# ReuseBlock_opa2450_2024-11-16.net
KiCad netlist of a schematic drawn in EasyEDA Pro
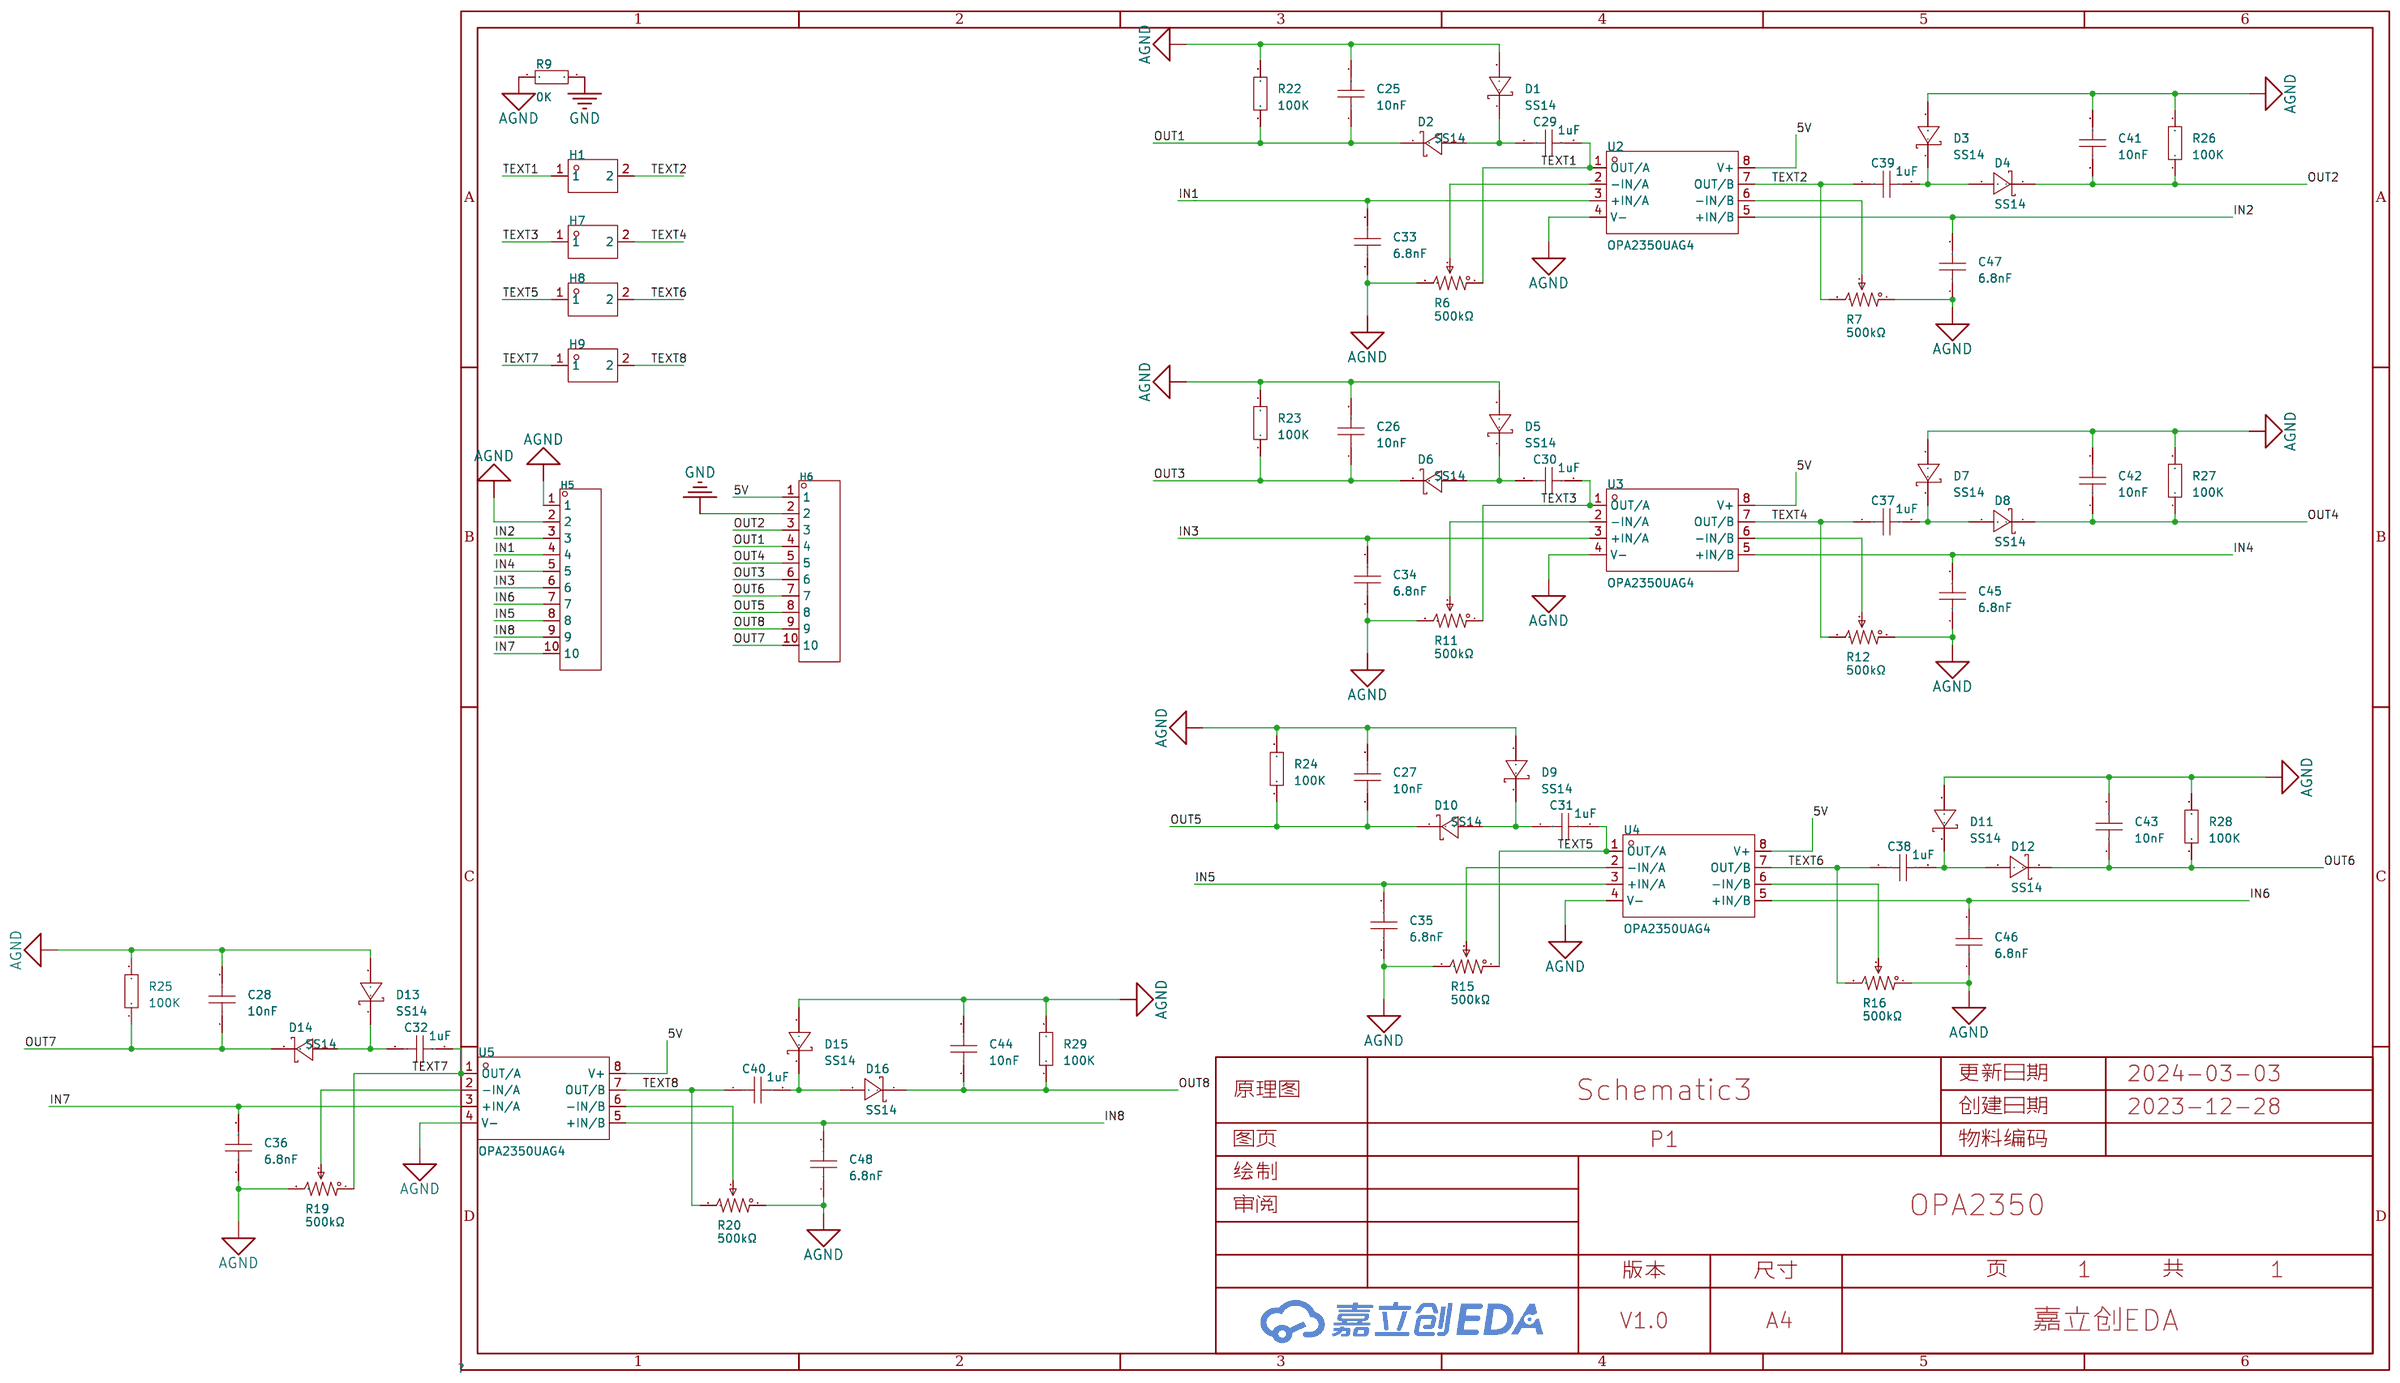
[diagram p0: schematic sheet]

(export (version "E")
  (design (tool "Eeschema 10.0.6"))
  (components
    (comp (ref "C25")
      (value "10nF")
      (footprint "easyedapro:C0603")
      (libsource (lib "easyedapro") (part "CapAcitance"))
    )
    (comp (ref "C26")
      (value "10nF")
      (footprint "easyedapro:C0603")
      (libsource (lib "easyedapro") (part "CapAcitance"))
    )
    (comp (ref "C27")
      (value "10nF")
      (footprint "easyedapro:C0603")
      (libsource (lib "easyedapro") (part "CapAcitance"))
    )
    (comp (ref "C28")
      (value "10nF")
      (footprint "easyedapro:C0603")
      (libsource (lib "easyedapro") (part "CapAcitance"))
    )
    (comp (ref "C29")
      (value "1uF")
      (footprint "easyedapro:C0603")
      (libsource (lib "easyedapro") (part "CapAcitance"))
    )
    (comp (ref "C30")
      (value "1uF")
      (footprint "easyedapro:C0603")
      (libsource (lib "easyedapro") (part "CapAcitance"))
    )
    (comp (ref "C31")
      (value "1uF")
      (footprint "easyedapro:C0603")
      (libsource (lib "easyedapro") (part "CapAcitance"))
    )
    (comp (ref "C32")
      (value "1uF")
      (footprint "easyedapro:C0603")
      (libsource (lib "easyedapro") (part "CapAcitance"))
    )
    (comp (ref "C33")
      (value "6.8nF")
      (footprint "easyedapro:C0603")
      (libsource (lib "easyedapro") (part "CapAcitance"))
    )
    (comp (ref "C34")
      (value "6.8nF")
      (footprint "easyedapro:C0603")
      (libsource (lib "easyedapro") (part "CapAcitance"))
    )
    (comp (ref "C35")
      (value "6.8nF")
      (footprint "easyedapro:C0603")
      (libsource (lib "easyedapro") (part "CapAcitance"))
    )
    (comp (ref "C36")
      (value "6.8nF")
      (footprint "easyedapro:C0603")
      (libsource (lib "easyedapro") (part "CapAcitance"))
    )
    (comp (ref "C37")
      (value "1uF")
      (footprint "easyedapro:C0603")
      (libsource (lib "easyedapro") (part "CapAcitance"))
    )
    (comp (ref "C38")
      (value "1uF")
      (footprint "easyedapro:C0603")
      (libsource (lib "easyedapro") (part "CapAcitance"))
    )
    (comp (ref "C39")
      (value "1uF")
      (footprint "easyedapro:C0603")
      (libsource (lib "easyedapro") (part "CapAcitance"))
    )
    (comp (ref "C40")
      (value "1uF")
      (footprint "easyedapro:C0603")
      (libsource (lib "easyedapro") (part "CapAcitance"))
    )
    (comp (ref "C41")
      (value "10nF")
      (footprint "easyedapro:C0603")
      (libsource (lib "easyedapro") (part "CapAcitance"))
    )
    (comp (ref "C42")
      (value "10nF")
      (footprint "easyedapro:C0603")
      (libsource (lib "easyedapro") (part "CapAcitance"))
    )
    (comp (ref "C43")
      (value "10nF")
      (footprint "easyedapro:C0603")
      (libsource (lib "easyedapro") (part "CapAcitance"))
    )
    (comp (ref "C44")
      (value "10nF")
      (footprint "easyedapro:C0603")
      (libsource (lib "easyedapro") (part "CapAcitance"))
    )
    (comp (ref "C45")
      (value "6.8nF")
      (footprint "easyedapro:C0603")
      (libsource (lib "easyedapro") (part "CapAcitance"))
    )
    (comp (ref "C46")
      (value "6.8nF")
      (footprint "easyedapro:C0603")
      (libsource (lib "easyedapro") (part "CapAcitance"))
    )
    (comp (ref "C47")
      (value "6.8nF")
      (footprint "easyedapro:C0603")
      (libsource (lib "easyedapro") (part "CapAcitance"))
    )
    (comp (ref "C48")
      (value "6.8nF")
      (footprint "easyedapro:C0603")
      (libsource (lib "easyedapro") (part "CapAcitance"))
    )
    (comp (ref "D1")
      (value "SS14")
      (fields (field (name "Manufacturer") "MDD"))
      (libsource (lib "easyedapro") (part "SS14-XZ"))
    )
    (comp (ref "D2")
      (value "SS14")
      (fields (field (name "Manufacturer") "MDD"))
      (libsource (lib "easyedapro") (part "SS14-XZ"))
    )
    (comp (ref "D3")
      (value "SS14")
      (fields (field (name "Manufacturer") "MDD"))
      (libsource (lib "easyedapro") (part "SS14-XZ"))
    )
    (comp (ref "D4")
      (value "SS14")
      (fields (field (name "Manufacturer") "MDD"))
      (libsource (lib "easyedapro") (part "SS14-XZ"))
    )
    (comp (ref "D5")
      (value "SS14")
      (fields (field (name "Manufacturer") "MDD"))
      (libsource (lib "easyedapro") (part "SS14-XZ"))
    )
    (comp (ref "D6")
      (value "SS14")
      (fields (field (name "Manufacturer") "MDD"))
      (libsource (lib "easyedapro") (part "SS14-XZ"))
    )
    (comp (ref "D7")
      (value "SS14")
      (fields (field (name "Manufacturer") "MDD"))
      (libsource (lib "easyedapro") (part "SS14-XZ"))
    )
    (comp (ref "D8")
      (value "SS14")
      (fields (field (name "Manufacturer") "MDD"))
      (libsource (lib "easyedapro") (part "SS14-XZ"))
    )
    (comp (ref "D9")
      (value "SS14")
      (fields (field (name "Manufacturer") "MDD"))
      (libsource (lib "easyedapro") (part "SS14-XZ"))
    )
    (comp (ref "D10")
      (value "SS14")
      (fields (field (name "Manufacturer") "MDD"))
      (libsource (lib "easyedapro") (part "SS14-XZ"))
    )
    (comp (ref "D11")
      (value "SS14")
      (fields (field (name "Manufacturer") "MDD"))
      (libsource (lib "easyedapro") (part "SS14-XZ"))
    )
    (comp (ref "D12")
      (value "SS14")
      (fields (field (name "Manufacturer") "MDD"))
      (libsource (lib "easyedapro") (part "SS14-XZ"))
    )
    (comp (ref "D13")
      (value "SS14")
      (fields (field (name "Manufacturer") "MDD"))
      (libsource (lib "easyedapro") (part "SS14-XZ"))
    )
    (comp (ref "D14")
      (value "SS14")
      (fields (field (name "Manufacturer") "MDD"))
      (libsource (lib "easyedapro") (part "SS14-XZ"))
    )
    (comp (ref "D15")
      (value "SS14")
      (fields (field (name "Manufacturer") "MDD"))
      (libsource (lib "easyedapro") (part "SS14-XZ"))
    )
    (comp (ref "D16")
      (value "SS14")
      (fields (field (name "Manufacturer") "MDD"))
      (libsource (lib "easyedapro") (part "SS14-XZ"))
    )
    (comp (ref "H1")
      (value "~")
      (footprint "easyedapro:HDR-TH_2P-P2.54-V-M-2")
      (libsource (lib "easyedapro") (part "HDR-M-2.54_2x1"))
    )
    (comp (ref "H5")
      (value "~")
      (footprint "easyedapro:HDR-TH_10P-P2.54-V-M-1")
      (libsource (lib "easyedapro") (part "Header-Male-2.54_1x10"))
    )
    (comp (ref "H6")
      (value "~")
      (footprint "easyedapro:HDR-TH_10P-P2.54-V-M-1")
      (libsource (lib "easyedapro") (part "Header-Male-2.54_1x10"))
    )
    (comp (ref "H7")
      (value "~")
      (footprint "easyedapro:HDR-TH_2P-P2.54-V-M-2")
      (libsource (lib "easyedapro") (part "HDR-M-2.54_2x1"))
    )
    (comp (ref "H8")
      (value "~")
      (footprint "easyedapro:HDR-TH_2P-P2.54-V-M-2")
      (libsource (lib "easyedapro") (part "HDR-M-2.54_2x1"))
    )
    (comp (ref "H9")
      (value "~")
      (footprint "easyedapro:HDR-TH_2P-P2.54-V-M-2")
      (libsource (lib "easyedapro") (part "HDR-M-2.54_2x1"))
    )
    (comp (ref "R6")
      (value "500kΩ")
      (footprint "easyedapro:RES-ADJ-TH_3P-L9.5-W4.85-P2.50-BL-BS")
      (description "阻值:500kΩ;精度:±10%;")
      (fields (field (name "Manufacturer Part") "3296W-1-504") (field (name "Manufacturer") "BOCHEN(博晨)"))
      (libsource (lib "easyedapro") (part "3296W-1-504"))
    )
    (comp (ref "R7")
      (value "500kΩ")
      (footprint "easyedapro:RES-ADJ-TH_3P-L9.5-W4.85-P2.50-BL-BS")
      (description "阻值:500kΩ;精度:±10%;")
      (fields (field (name "Manufacturer Part") "3296W-1-504") (field (name "Manufacturer") "BOCHEN(博晨)"))
      (libsource (lib "easyedapro") (part "3296W-1-504"))
    )
    (comp (ref "R9") (value "0K") (footprint "easyedapro:R0603") (libsource (lib "easyedapro") (part "电阻")))
    (comp (ref "R11")
      (value "500kΩ")
      (footprint "easyedapro:RES-ADJ-TH_3P-L9.5-W4.85-P2.50-BL-BS")
      (description "阻值:500kΩ;精度:±10%;")
      (fields (field (name "Manufacturer Part") "3296W-1-504") (field (name "Manufacturer") "BOCHEN(博晨)"))
      (libsource (lib "easyedapro") (part "3296W-1-504"))
    )
    (comp (ref "R12")
      (value "500kΩ")
      (footprint "easyedapro:RES-ADJ-TH_3P-L9.5-W4.85-P2.50-BL-BS")
      (description "阻值:500kΩ;精度:±10%;")
      (fields (field (name "Manufacturer Part") "3296W-1-504") (field (name "Manufacturer") "BOCHEN(博晨)"))
      (libsource (lib "easyedapro") (part "3296W-1-504"))
    )
    (comp (ref "R15")
      (value "500kΩ")
      (footprint "easyedapro:RES-ADJ-TH_3P-L9.5-W4.85-P2.50-BL-BS")
      (description "阻值:500kΩ;精度:±10%;")
      (fields (field (name "Manufacturer Part") "3296W-1-504") (field (name "Manufacturer") "BOCHEN(博晨)"))
      (libsource (lib "easyedapro") (part "3296W-1-504"))
    )
    (comp (ref "R16")
      (value "500kΩ")
      (footprint "easyedapro:RES-ADJ-TH_3P-L9.5-W4.85-P2.50-BL-BS")
      (description "阻值:500kΩ;精度:±10%;")
      (fields (field (name "Manufacturer Part") "3296W-1-504") (field (name "Manufacturer") "BOCHEN(博晨)"))
      (libsource (lib "easyedapro") (part "3296W-1-504"))
    )
    (comp (ref "R19")
      (value "500kΩ")
      (footprint "easyedapro:RES-ADJ-TH_3P-L9.5-W4.85-P2.50-BL-BS")
      (description "阻值:500kΩ;精度:±10%;")
      (fields (field (name "Manufacturer Part") "3296W-1-504") (field (name "Manufacturer") "BOCHEN(博晨)"))
      (libsource (lib "easyedapro") (part "3296W-1-504"))
    )
    (comp (ref "R20")
      (value "500kΩ")
      (footprint "easyedapro:RES-ADJ-TH_3P-L9.5-W4.85-P2.50-BL-BS")
      (description "阻值:500kΩ;精度:±10%;")
      (fields (field (name "Manufacturer Part") "3296W-1-504") (field (name "Manufacturer") "BOCHEN(博晨)"))
      (libsource (lib "easyedapro") (part "3296W-1-504"))
    )
    (comp (ref "R22")
      (value "100K")
      (footprint "easyedapro:R0603")
      (libsource (lib "easyedapro") (part "电阻"))
    )
    (comp (ref "R23")
      (value "100K")
      (footprint "easyedapro:R0603")
      (libsource (lib "easyedapro") (part "电阻"))
    )
    (comp (ref "R24")
      (value "100K")
      (footprint "easyedapro:R0603")
      (libsource (lib "easyedapro") (part "电阻"))
    )
    (comp (ref "R25")
      (value "100K")
      (footprint "easyedapro:R0603")
      (libsource (lib "easyedapro") (part "电阻"))
    )
    (comp (ref "R26")
      (value "100K")
      (footprint "easyedapro:R0603")
      (libsource (lib "easyedapro") (part "电阻"))
    )
    (comp (ref "R27")
      (value "100K")
      (footprint "easyedapro:R0603")
      (libsource (lib "easyedapro") (part "电阻"))
    )
    (comp (ref "R28")
      (value "100K")
      (footprint "easyedapro:R0603")
      (libsource (lib "easyedapro") (part "电阻"))
    )
    (comp (ref "R29")
      (value "100K")
      (footprint "easyedapro:R0603")
      (libsource (lib "easyedapro") (part "电阻"))
    )
    (comp (ref "U2")
      (value "OPA2350UAG4")
      (footprint "easyedapro:SOIC-8_L4.9-W3.9-P1.27-LS6.0-BL")
      (description "双路单电源、轨到轨、高速、低噪声运算放大器 8-SOIC -40 to 85")
      (fields (field (name "Manufacturer") "TI(德州仪器)"))
      (libsource (lib "easyedapro") (part "OPA2350UAG4"))
    )
    (comp (ref "U3")
      (value "OPA2350UAG4")
      (footprint "easyedapro:SOIC-8_L4.9-W3.9-P1.27-LS6.0-BL")
      (description "双路单电源、轨到轨、高速、低噪声运算放大器 8-SOIC -40 to 85")
      (fields (field (name "Manufacturer") "TI(德州仪器)"))
      (libsource (lib "easyedapro") (part "OPA2350UAG4"))
    )
    (comp (ref "U4")
      (value "OPA2350UAG4")
      (footprint "easyedapro:SOIC-8_L4.9-W3.9-P1.27-LS6.0-BL")
      (description "双路单电源、轨到轨、高速、低噪声运算放大器 8-SOIC -40 to 85")
      (fields (field (name "Manufacturer") "TI(德州仪器)"))
      (libsource (lib "easyedapro") (part "OPA2350UAG4"))
    )
    (comp (ref "U5")
      (value "OPA2350UAG4")
      (footprint "easyedapro:SOIC-8_L4.9-W3.9-P1.27-LS6.0-BL")
      (description "双路单电源、轨到轨、高速、低噪声运算放大器 8-SOIC -40 to 85")
      (fields (field (name "Manufacturer") "TI(德州仪器)"))
      (libsource (lib "easyedapro") (part "OPA2350UAG4"))
    )
  )
  (nets
    (net (code "1") (name "/5V") (class "Default")
      (node (ref "H6") (pin "1") (pinfunction "1_1") (pintype "input"))
      (node (ref "U2") (pin "8") (pinfunction "V+_8") (pintype "input"))
      (node (ref "U3") (pin "8") (pinfunction "V+_8") (pintype "input"))
      (node (ref "U4") (pin "8") (pinfunction "V+_8") (pintype "input"))
      (node (ref "U5") (pin "8") (pinfunction "V+_8") (pintype "input"))
    )
    (net (code "2") (name "/IN1") (class "Default")
      (node (ref "C33") (pin "2") (pinfunction "2_2") (pintype "input"))
      (node (ref "H5") (pin "4") (pinfunction "4_4") (pintype "input"))
      (node (ref "U2") (pin "3") (pinfunction "+IN/A_3") (pintype "input"))
    )
    (net (code "3") (name "/IN2") (class "Default")
      (node (ref "C47") (pin "2") (pinfunction "2_2") (pintype "input"))
      (node (ref "H5") (pin "3") (pinfunction "3_3") (pintype "input"))
      (node (ref "U2") (pin "5") (pinfunction "+IN/B_5") (pintype "input"))
    )
    (net (code "4") (name "/IN3") (class "Default")
      (node (ref "C34") (pin "2") (pinfunction "2_2") (pintype "input"))
      (node (ref "H5") (pin "6") (pinfunction "6_6") (pintype "input"))
      (node (ref "U3") (pin "3") (pinfunction "+IN/A_3") (pintype "input"))
    )
    (net (code "5") (name "/IN4") (class "Default")
      (node (ref "C45") (pin "2") (pinfunction "2_2") (pintype "input"))
      (node (ref "H5") (pin "5") (pinfunction "5_5") (pintype "input"))
      (node (ref "U3") (pin "5") (pinfunction "+IN/B_5") (pintype "input"))
    )
    (net (code "6") (name "/IN5") (class "Default")
      (node (ref "C35") (pin "2") (pinfunction "2_2") (pintype "input"))
      (node (ref "H5") (pin "8") (pinfunction "8_8") (pintype "input"))
      (node (ref "U4") (pin "3") (pinfunction "+IN/A_3") (pintype "input"))
    )
    (net (code "7") (name "/IN6") (class "Default")
      (node (ref "C46") (pin "2") (pinfunction "2_2") (pintype "input"))
      (node (ref "H5") (pin "7") (pinfunction "7_7") (pintype "input"))
      (node (ref "U4") (pin "5") (pinfunction "+IN/B_5") (pintype "input"))
    )
    (net (code "8") (name "/IN7") (class "Default")
      (node (ref "C36") (pin "2") (pinfunction "2_2") (pintype "input"))
      (node (ref "H5") (pin "10") (pinfunction "10_10") (pintype "input"))
      (node (ref "U5") (pin "3") (pinfunction "+IN/A_3") (pintype "input"))
    )
    (net (code "9") (name "/IN8") (class "Default")
      (node (ref "C48") (pin "2") (pinfunction "2_2") (pintype "input"))
      (node (ref "H5") (pin "9") (pinfunction "9_9") (pintype "input"))
      (node (ref "U5") (pin "5") (pinfunction "+IN/B_5") (pintype "input"))
    )
    (net (code "10") (name "/OUT1") (class "Default")
      (node (ref "C25") (pin "1") (pinfunction "1_1") (pintype "input"))
      (node (ref "D2") (pin "1") (pinfunction "K_1") (pintype "input"))
      (node (ref "H6") (pin "4") (pinfunction "4_4") (pintype "input"))
      (node (ref "R22") (pin "1") (pinfunction "1_1") (pintype "input"))
    )
    (net (code "11") (name "/OUT2") (class "Default")
      (node (ref "C41") (pin "1") (pinfunction "1_1") (pintype "input"))
      (node (ref "D4") (pin "1") (pinfunction "K_1") (pintype "input"))
      (node (ref "H6") (pin "3") (pinfunction "3_3") (pintype "input"))
      (node (ref "R26") (pin "1") (pinfunction "1_1") (pintype "input"))
    )
    (net (code "12") (name "/OUT3") (class "Default")
      (node (ref "C26") (pin "1") (pinfunction "1_1") (pintype "input"))
      (node (ref "D6") (pin "1") (pinfunction "K_1") (pintype "input"))
      (node (ref "H6") (pin "6") (pinfunction "6_6") (pintype "input"))
      (node (ref "R23") (pin "1") (pinfunction "1_1") (pintype "input"))
    )
    (net (code "13") (name "/OUT4") (class "Default")
      (node (ref "C42") (pin "1") (pinfunction "1_1") (pintype "input"))
      (node (ref "D8") (pin "1") (pinfunction "K_1") (pintype "input"))
      (node (ref "H6") (pin "5") (pinfunction "5_5") (pintype "input"))
      (node (ref "R27") (pin "1") (pinfunction "1_1") (pintype "input"))
    )
    (net (code "14") (name "/OUT5") (class "Default")
      (node (ref "C27") (pin "1") (pinfunction "1_1") (pintype "input"))
      (node (ref "D10") (pin "1") (pinfunction "K_1") (pintype "input"))
      (node (ref "H6") (pin "8") (pinfunction "8_8") (pintype "input"))
      (node (ref "R24") (pin "1") (pinfunction "1_1") (pintype "input"))
    )
    (net (code "15") (name "/OUT6") (class "Default")
      (node (ref "C43") (pin "1") (pinfunction "1_1") (pintype "input"))
      (node (ref "D12") (pin "1") (pinfunction "K_1") (pintype "input"))
      (node (ref "H6") (pin "7") (pinfunction "7_7") (pintype "input"))
      (node (ref "R28") (pin "1") (pinfunction "1_1") (pintype "input"))
    )
    (net (code "16") (name "/OUT7") (class "Default")
      (node (ref "C28") (pin "1") (pinfunction "1_1") (pintype "input"))
      (node (ref "D14") (pin "1") (pinfunction "K_1") (pintype "input"))
      (node (ref "H6") (pin "10") (pinfunction "10_10") (pintype "input"))
      (node (ref "R25") (pin "1") (pinfunction "1_1") (pintype "input"))
    )
    (net (code "17") (name "/OUT8") (class "Default")
      (node (ref "C44") (pin "1") (pinfunction "1_1") (pintype "input"))
      (node (ref "D16") (pin "1") (pinfunction "K_1") (pintype "input"))
      (node (ref "H6") (pin "9") (pinfunction "9_9") (pintype "input"))
      (node (ref "R29") (pin "1") (pinfunction "1_1") (pintype "input"))
    )
    (net (code "18") (name "/TEXT1") (class "Default")
      (node (ref "C29") (pin "2") (pinfunction "2_2") (pintype "input"))
      (node (ref "H1") (pin "1") (pinfunction "1_1") (pintype "input"))
      (node (ref "R6") (pin "1") (pinfunction "1_1") (pintype "input"))
      (node (ref "U2") (pin "1") (pinfunction "OUT/A_1") (pintype "input"))
    )
    (net (code "19") (name "/TEXT2") (class "Default")
      (node (ref "C39") (pin "1") (pinfunction "1_1") (pintype "input"))
      (node (ref "H1") (pin "2") (pinfunction "2_2") (pintype "input"))
      (node (ref "R7") (pin "3") (pinfunction "3_3") (pintype "input"))
      (node (ref "U2") (pin "7") (pinfunction "OUT/B_7") (pintype "input"))
    )
    (net (code "20") (name "/TEXT3") (class "Default")
      (node (ref "C30") (pin "2") (pinfunction "2_2") (pintype "input"))
      (node (ref "H7") (pin "1") (pinfunction "1_1") (pintype "input"))
      (node (ref "R11") (pin "1") (pinfunction "1_1") (pintype "input"))
      (node (ref "U3") (pin "1") (pinfunction "OUT/A_1") (pintype "input"))
    )
    (net (code "21") (name "/TEXT4") (class "Default")
      (node (ref "C37") (pin "1") (pinfunction "1_1") (pintype "input"))
      (node (ref "H7") (pin "2") (pinfunction "2_2") (pintype "input"))
      (node (ref "R12") (pin "3") (pinfunction "3_3") (pintype "input"))
      (node (ref "U3") (pin "7") (pinfunction "OUT/B_7") (pintype "input"))
    )
    (net (code "22") (name "/TEXT5") (class "Default")
      (node (ref "C31") (pin "2") (pinfunction "2_2") (pintype "input"))
      (node (ref "H8") (pin "1") (pinfunction "1_1") (pintype "input"))
      (node (ref "R15") (pin "1") (pinfunction "1_1") (pintype "input"))
      (node (ref "U4") (pin "1") (pinfunction "OUT/A_1") (pintype "input"))
    )
    (net (code "23") (name "/TEXT6") (class "Default")
      (node (ref "C38") (pin "1") (pinfunction "1_1") (pintype "input"))
      (node (ref "H8") (pin "2") (pinfunction "2_2") (pintype "input"))
      (node (ref "R16") (pin "3") (pinfunction "3_3") (pintype "input"))
      (node (ref "U4") (pin "7") (pinfunction "OUT/B_7") (pintype "input"))
    )
    (net (code "24") (name "/TEXT7") (class "Default")
      (node (ref "C32") (pin "2") (pinfunction "2_2") (pintype "input"))
      (node (ref "H9") (pin "1") (pinfunction "1_1") (pintype "input"))
      (node (ref "R19") (pin "1") (pinfunction "1_1") (pintype "input"))
      (node (ref "U5") (pin "1") (pinfunction "OUT/A_1") (pintype "input"))
    )
    (net (code "25") (name "/TEXT8") (class "Default")
      (node (ref "C40") (pin "1") (pinfunction "1_1") (pintype "input"))
      (node (ref "H9") (pin "2") (pinfunction "2_2") (pintype "input"))
      (node (ref "R20") (pin "3") (pinfunction "3_3") (pintype "input"))
      (node (ref "U5") (pin "7") (pinfunction "OUT/B_7") (pintype "input"))
    )
    (net (code "26") (name "AGND") (class "Default")
      (node (ref "C25") (pin "2") (pinfunction "2_2") (pintype "input"))
      (node (ref "C26") (pin "2") (pinfunction "2_2") (pintype "input"))
      (node (ref "C27") (pin "2") (pinfunction "2_2") (pintype "input"))
      (node (ref "C28") (pin "2") (pinfunction "2_2") (pintype "input"))
      (node (ref "C33") (pin "1") (pinfunction "1_1") (pintype "input"))
      (node (ref "C34") (pin "1") (pinfunction "1_1") (pintype "input"))
      (node (ref "C35") (pin "1") (pinfunction "1_1") (pintype "input"))
      (node (ref "C36") (pin "1") (pinfunction "1_1") (pintype "input"))
      (node (ref "C41") (pin "2") (pinfunction "2_2") (pintype "input"))
      (node (ref "C42") (pin "2") (pinfunction "2_2") (pintype "input"))
      (node (ref "C43") (pin "2") (pinfunction "2_2") (pintype "input"))
      (node (ref "C44") (pin "2") (pinfunction "2_2") (pintype "input"))
      (node (ref "C45") (pin "1") (pinfunction "1_1") (pintype "input"))
      (node (ref "C46") (pin "1") (pinfunction "1_1") (pintype "input"))
      (node (ref "C47") (pin "1") (pinfunction "1_1") (pintype "input"))
      (node (ref "C48") (pin "1") (pinfunction "1_1") (pintype "input"))
      (node (ref "D1") (pin "2") (pinfunction "A_2") (pintype "input"))
      (node (ref "D11") (pin "2") (pinfunction "A_2") (pintype "input"))
      (node (ref "D13") (pin "2") (pinfunction "A_2") (pintype "input"))
      (node (ref "D15") (pin "2") (pinfunction "A_2") (pintype "input"))
      (node (ref "D3") (pin "2") (pinfunction "A_2") (pintype "input"))
      (node (ref "D5") (pin "2") (pinfunction "A_2") (pintype "input"))
      (node (ref "D7") (pin "2") (pinfunction "A_2") (pintype "input"))
      (node (ref "D9") (pin "2") (pinfunction "A_2") (pintype "input"))
      (node (ref "H5") (pin "1") (pinfunction "1_1") (pintype "input"))
      (node (ref "H5") (pin "2") (pinfunction "2_2") (pintype "input"))
      (node (ref "R11") (pin "3") (pinfunction "3_3") (pintype "input"))
      (node (ref "R12") (pin "1") (pinfunction "1_1") (pintype "input"))
      (node (ref "R15") (pin "3") (pinfunction "3_3") (pintype "input"))
      (node (ref "R16") (pin "1") (pinfunction "1_1") (pintype "input"))
      (node (ref "R19") (pin "3") (pinfunction "3_3") (pintype "input"))
      (node (ref "R20") (pin "1") (pinfunction "1_1") (pintype "input"))
      (node (ref "R22") (pin "2") (pinfunction "2_2") (pintype "input"))
      (node (ref "R23") (pin "2") (pinfunction "2_2") (pintype "input"))
      (node (ref "R24") (pin "2") (pinfunction "2_2") (pintype "input"))
      (node (ref "R25") (pin "2") (pinfunction "2_2") (pintype "input"))
      (node (ref "R26") (pin "2") (pinfunction "2_2") (pintype "input"))
      (node (ref "R27") (pin "2") (pinfunction "2_2") (pintype "input"))
      (node (ref "R28") (pin "2") (pinfunction "2_2") (pintype "input"))
      (node (ref "R29") (pin "2") (pinfunction "2_2") (pintype "input"))
      (node (ref "R6") (pin "3") (pinfunction "3_3") (pintype "input"))
      (node (ref "R7") (pin "1") (pinfunction "1_1") (pintype "input"))
      (node (ref "R9") (pin "1") (pinfunction "1_1") (pintype "input"))
      (node (ref "U2") (pin "4") (pinfunction "V-_4") (pintype "input"))
      (node (ref "U3") (pin "4") (pinfunction "V-_4") (pintype "input"))
      (node (ref "U4") (pin "4") (pinfunction "V-_4") (pintype "input"))
      (node (ref "U5") (pin "4") (pinfunction "V-_4") (pintype "input"))
    )
    (net (code "27") (name "GND") (class "Default")
      (node (ref "H6") (pin "2") (pinfunction "2_2") (pintype "input"))
      (node (ref "R9") (pin "2") (pinfunction "2_2") (pintype "input"))
    )
    (net (code "28") (name "Net-(D1-K)") (class "Default")
      (node (ref "C29") (pin "1") (pinfunction "1_1") (pintype "input"))
      (node (ref "D1") (pin "1") (pinfunction "K_1") (pintype "input"))
      (node (ref "D2") (pin "2") (pinfunction "A_2") (pintype "input"))
    )
    (net (code "29") (name "Net-(D3-K)") (class "Default")
      (node (ref "C39") (pin "2") (pinfunction "2_2") (pintype "input"))
      (node (ref "D3") (pin "1") (pinfunction "K_1") (pintype "input"))
      (node (ref "D4") (pin "2") (pinfunction "A_2") (pintype "input"))
    )
    (net (code "30") (name "Net-(D5-K)") (class "Default")
      (node (ref "C30") (pin "1") (pinfunction "1_1") (pintype "input"))
      (node (ref "D5") (pin "1") (pinfunction "K_1") (pintype "input"))
      (node (ref "D6") (pin "2") (pinfunction "A_2") (pintype "input"))
    )
    (net (code "31") (name "Net-(D7-K)") (class "Default")
      (node (ref "C37") (pin "2") (pinfunction "2_2") (pintype "input"))
      (node (ref "D7") (pin "1") (pinfunction "K_1") (pintype "input"))
      (node (ref "D8") (pin "2") (pinfunction "A_2") (pintype "input"))
    )
    (net (code "32") (name "Net-(D10-A)") (class "Default")
      (node (ref "C31") (pin "1") (pinfunction "1_1") (pintype "input"))
      (node (ref "D10") (pin "2") (pinfunction "A_2") (pintype "input"))
      (node (ref "D9") (pin "1") (pinfunction "K_1") (pintype "input"))
    )
    (net (code "33") (name "Net-(D11-K)") (class "Default")
      (node (ref "C38") (pin "2") (pinfunction "2_2") (pintype "input"))
      (node (ref "D11") (pin "1") (pinfunction "K_1") (pintype "input"))
      (node (ref "D12") (pin "2") (pinfunction "A_2") (pintype "input"))
    )
    (net (code "34") (name "Net-(D13-K)") (class "Default")
      (node (ref "C32") (pin "1") (pinfunction "1_1") (pintype "input"))
      (node (ref "D13") (pin "1") (pinfunction "K_1") (pintype "input"))
      (node (ref "D14") (pin "2") (pinfunction "A_2") (pintype "input"))
    )
    (net (code "35") (name "Net-(D15-K)") (class "Default")
      (node (ref "C40") (pin "2") (pinfunction "2_2") (pintype "input"))
      (node (ref "D15") (pin "1") (pinfunction "K_1") (pintype "input"))
      (node (ref "D16") (pin "2") (pinfunction "A_2") (pintype "input"))
    )
    (net (code "36") (name "Net-(U2--IN{slash}A)") (class "Default")
      (node (ref "R6") (pin "2") (pinfunction "2_2") (pintype "input"))
      (node (ref "U2") (pin "2") (pinfunction "-IN/A_2") (pintype "input"))
    )
    (net (code "37") (name "Net-(U2--IN{slash}B)") (class "Default")
      (node (ref "R7") (pin "2") (pinfunction "2_2") (pintype "input"))
      (node (ref "U2") (pin "6") (pinfunction "-IN/B_6") (pintype "input"))
    )
    (net (code "38") (name "Net-(U3--IN{slash}A)") (class "Default")
      (node (ref "R11") (pin "2") (pinfunction "2_2") (pintype "input"))
      (node (ref "U3") (pin "2") (pinfunction "-IN/A_2") (pintype "input"))
    )
    (net (code "39") (name "Net-(U3--IN{slash}B)") (class "Default")
      (node (ref "R12") (pin "2") (pinfunction "2_2") (pintype "input"))
      (node (ref "U3") (pin "6") (pinfunction "-IN/B_6") (pintype "input"))
    )
    (net (code "40") (name "Net-(U4--IN{slash}A)") (class "Default")
      (node (ref "R15") (pin "2") (pinfunction "2_2") (pintype "input"))
      (node (ref "U4") (pin "2") (pinfunction "-IN/A_2") (pintype "input"))
    )
    (net (code "41") (name "Net-(U4--IN{slash}B)") (class "Default")
      (node (ref "R16") (pin "2") (pinfunction "2_2") (pintype "input"))
      (node (ref "U4") (pin "6") (pinfunction "-IN/B_6") (pintype "input"))
    )
    (net (code "42") (name "Net-(U5--IN{slash}A)") (class "Default")
      (node (ref "R19") (pin "2") (pinfunction "2_2") (pintype "input"))
      (node (ref "U5") (pin "2") (pinfunction "-IN/A_2") (pintype "input"))
    )
    (net (code "43") (name "Net-(U5--IN{slash}B)") (class "Default")
      (node (ref "R20") (pin "2") (pinfunction "2_2") (pintype "input"))
      (node (ref "U5") (pin "6") (pinfunction "-IN/B_6") (pintype "input"))
    )
  )
)
